# Led-7Segment-Switch.net
KiCad netlist of a schematic drawn in Altium Designer
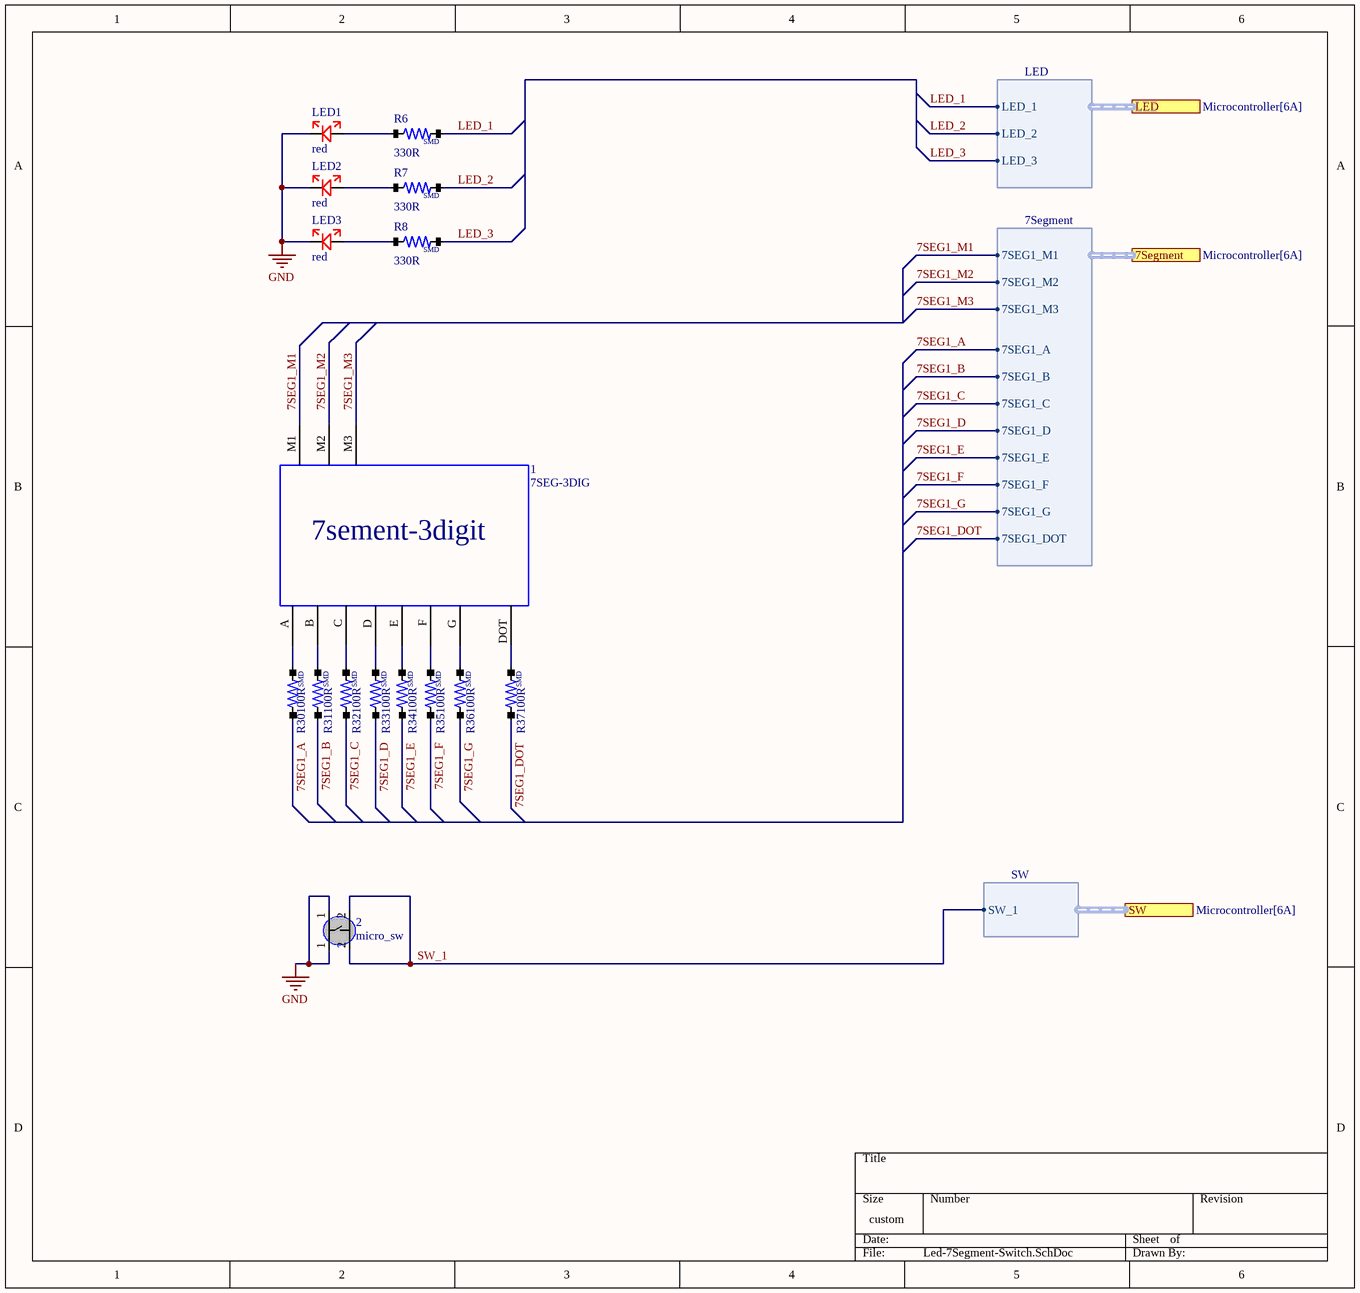
[diagram p0: Led-7Segment-Switch.SchDoc]

(export (version "E")
  (design (tool "Eeschema 10.0.6"))
  (components
    (comp (ref "1")
      (value "7SEG-3DIG")
      (footprint "7seg-3d")
      (libsource (lib "kave-eng-pro") (part "7SEG-3DIG"))
    )
    (comp (ref "2")
      (value "micro_sw")
      (footprint "micro_switch_smd")
      (libsource (lib "kave-eng-pro") (part "micro_sw"))
    )
    (comp (ref "LED1")
      (value "red")
      (footprint "LED/0805")
      (libsource (lib "kave-eng-pro") (part "LED-1COLER"))
    )
    (comp (ref "LED2")
      (value "red")
      (footprint "LED/0805")
      (libsource (lib "kave-eng-pro") (part "LED-1COLER"))
    )
    (comp (ref "LED3")
      (value "red")
      (footprint "LED/0805")
      (libsource (lib "kave-eng-pro") (part "LED-1COLER"))
    )
    (comp (ref "R6") (value "330R") (footprint "RES/0603") (libsource (lib "") (part "RES/SMD_1")))
    (comp (ref "R7") (value "330R") (footprint "RES/0603") (libsource (lib "") (part "RES/SMD_1")))
    (comp (ref "R8") (value "330R") (footprint "RES/0603") (libsource (lib "") (part "RES/SMD_1")))
    (comp (ref "R30") (value "100R") (footprint "RES/0603") (libsource (lib "kave-eng-pro") (part "RES/SMD")))
    (comp (ref "R31") (value "100R") (footprint "RES/0603") (libsource (lib "kave-eng-pro") (part "RES/SMD")))
    (comp (ref "R32") (value "100R") (footprint "RES/0603") (libsource (lib "kave-eng-pro") (part "RES/SMD")))
    (comp (ref "R33") (value "100R") (footprint "RES/0603") (libsource (lib "") (part "RES/SMD_3")))
    (comp (ref "R34") (value "100R") (footprint "RES/0603") (libsource (lib "kave-eng-pro") (part "RES/SMD")))
    (comp (ref "R35") (value "100R") (footprint "RES/0603") (libsource (lib "kave-eng-pro") (part "RES/SMD")))
    (comp (ref "R36") (value "100R") (footprint "RES/0603") (libsource (lib "kave-eng-pro") (part "RES/SMD")))
    (comp (ref "R37") (value "100R") (footprint "RES/0603") (libsource (lib "") (part "RES/SMD_2")))
  )
  (nets
    (net (code "4") (name "/7SEG1_A") (class "Default")
      (node (ref "R30") (pin "1") (pinfunction "1_1") (pintype "passive"))
    )
    (net (code "5") (name "/7SEG1_B") (class "Default")
      (node (ref "R31") (pin "1") (pinfunction "1_1") (pintype "passive"))
    )
    (net (code "6") (name "/7SEG1_C") (class "Default")
      (node (ref "R32") (pin "1") (pinfunction "1_1") (pintype "passive"))
    )
    (net (code "7") (name "/7SEG1_D") (class "Default")
      (node (ref "R33") (pin "1") (pinfunction "1_1") (pintype "passive"))
    )
    (net (code "8") (name "/7SEG1_DOT") (class "Default")
      (node (ref "R37") (pin "1") (pinfunction "1_1") (pintype "passive"))
    )
    (net (code "9") (name "/7SEG1_E") (class "Default")
      (node (ref "R34") (pin "1") (pinfunction "1_1") (pintype "passive"))
    )
    (net (code "10") (name "/7SEG1_F") (class "Default")
      (node (ref "R35") (pin "1") (pinfunction "1_1") (pintype "passive"))
    )
    (net (code "11") (name "/7SEG1_G") (class "Default")
      (node (ref "R36") (pin "1") (pinfunction "1_1") (pintype "passive"))
    )
    (net (code "12") (name "/7SEG1_M1") (class "Default") (node (ref "1") (pin "M1") (pintype "passive")))
    (net (code "13") (name "/7SEG1_M2") (class "Default") (node (ref "1") (pin "M2") (pintype "passive")))
    (net (code "14") (name "/7SEG1_M3") (class "Default") (node (ref "1") (pin "M3") (pintype "passive")))
    (net (code "15") (name "/LED_1") (class "Default")
      (node (ref "R6") (pin "2") (pinfunction "2_2") (pintype "passive"))
    )
    (net (code "16") (name "/LED_2") (class "Default")
      (node (ref "R7") (pin "2") (pinfunction "2_2") (pintype "passive"))
    )
    (net (code "17") (name "/LED_3") (class "Default")
      (node (ref "R8") (pin "2") (pinfunction "2_2") (pintype "passive"))
    )
    (net (code "18") (name "/SW_1") (class "Default") (node (ref "2") (pin "2") (pintype "passive")))
    (net (code "22") (name "GND") (class "Default")
      (node (ref "2") (pin "1") (pintype "passive"))
      (node (ref "LED1") (pin "A") (pintype "passive"))
      (node (ref "LED2") (pin "A") (pintype "passive"))
      (node (ref "LED3") (pin "A") (pintype "passive"))
    )
    (net (code "23") (name "Net-(1-PadA)") (class "Default")
      (node (ref "1") (pin "A") (pintype "passive"))
      (node (ref "R30") (pin "2") (pinfunction "2_2") (pintype "passive"))
    )
    (net (code "24") (name "Net-(1-PadB)") (class "Default")
      (node (ref "1") (pin "B") (pintype "passive"))
      (node (ref "R31") (pin "2") (pinfunction "2_2") (pintype "passive"))
    )
    (net (code "25") (name "Net-(1-PadC)") (class "Default")
      (node (ref "1") (pin "C") (pintype "passive"))
      (node (ref "R32") (pin "2") (pinfunction "2_2") (pintype "passive"))
    )
    (net (code "26") (name "Net-(1-PadD)") (class "Default")
      (node (ref "1") (pin "D") (pintype "passive"))
      (node (ref "R33") (pin "2") (pinfunction "2_2") (pintype "passive"))
    )
    (net (code "27") (name "Net-(1-PadDOT)") (class "Default")
      (node (ref "1") (pin "DOT") (pintype "passive"))
      (node (ref "R37") (pin "2") (pinfunction "2_2") (pintype "passive"))
    )
    (net (code "28") (name "Net-(1-PadE)") (class "Default")
      (node (ref "1") (pin "E") (pintype "passive"))
      (node (ref "R34") (pin "2") (pinfunction "2_2") (pintype "passive"))
    )
    (net (code "29") (name "Net-(1-PadF)") (class "Default")
      (node (ref "1") (pin "F") (pintype "passive"))
      (node (ref "R35") (pin "2") (pinfunction "2_2") (pintype "passive"))
    )
    (net (code "30") (name "Net-(1-PadG)") (class "Default")
      (node (ref "1") (pin "G") (pintype "passive"))
      (node (ref "R36") (pin "2") (pinfunction "2_2") (pintype "passive"))
    )
    (net (code "31") (name "Net-(LED1-PadK)") (class "Default")
      (node (ref "LED1") (pin "K") (pintype "passive"))
      (node (ref "R6") (pin "1") (pinfunction "1_1") (pintype "passive"))
    )
    (net (code "32") (name "Net-(LED2-PadK)") (class "Default")
      (node (ref "LED2") (pin "K") (pintype "passive"))
      (node (ref "R7") (pin "1") (pinfunction "1_1") (pintype "passive"))
    )
    (net (code "33") (name "Net-(LED3-PadK)") (class "Default")
      (node (ref "LED3") (pin "K") (pintype "passive"))
      (node (ref "R8") (pin "1") (pinfunction "1_1") (pintype "passive"))
    )
  )
)
